# Output_des_Oszillators_Digitalisieren.net
KiCad netlist of a schematic drawn in Altium Designer
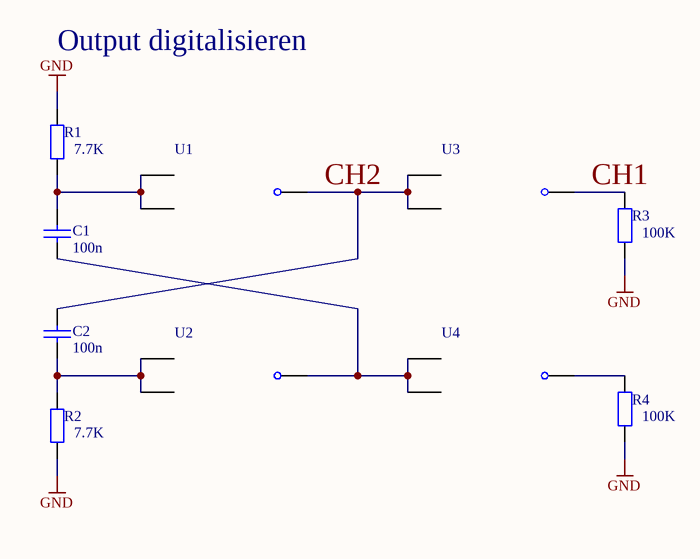
[diagram p0: Output des Oszillators Digitalisieren.SchDoc]

(export (version "E")
  (design (tool "Eeschema 10.0.6"))
  (components
    (comp (ref "C1")
      (value "100n")
      (description "Capacitor")
      (libsource (lib "Simulation Generic Components") (part "Capacitor"))
    )
    (comp (ref "C2")
      (value "100n")
      (description "Capacitor")
      (libsource (lib "Simulation Generic Components") (part "Capacitor"))
    )
    (comp (ref "R1")
      (value "7.7K")
      (footprint "AXIAL-0.4")
      (description "Resistor")
      (fields (field (name "Comment") "Res2") (field (name "PUBLISHER") "Altium Limited"))
      (libsource (lib "Miscellaneous Devices") (part "Res2"))
    )
    (comp (ref "R2")
      (value "7.7K")
      (footprint "AXIAL-0.4")
      (description "Resistor")
      (fields (field (name "Comment") "Res2") (field (name "PUBLISHER") "Altium Limited"))
      (libsource (lib "") (part "Res2_1"))
    )
    (comp (ref "R3")
      (value "100K")
      (footprint "AXIAL-0.4")
      (description "Resistor")
      (fields (field (name "Comment") "Res2") (field (name "PUBLISHER") "Altium Limited"))
      (libsource (lib "Miscellaneous Devices") (part "Res2"))
    )
    (comp (ref "R4")
      (value "100K")
      (footprint "AXIAL-0.4")
      (description "Resistor")
      (fields (field (name "Comment") "Res2") (field (name "PUBLISHER") "Altium Limited"))
      (libsource (lib "Miscellaneous Devices") (part "Res2"))
    )
    (comp (ref "U1")
      (value "Digital NAND Gate")
      (libsource (lib "Simulation Generic Components") (part "Digital NAND"))
    )
    (comp (ref "U2")
      (value "Digital NAND Gate")
      (libsource (lib "Simulation Generic Components") (part "Digital NAND"))
    )
    (comp (ref "U3")
      (value "Digital NAND Gate")
      (libsource (lib "Simulation Generic Components") (part "Digital NAND"))
    )
    (comp (ref "U4")
      (value "Digital NAND Gate")
      (libsource (lib "Simulation Generic Components") (part "Digital NAND"))
    )
  )
  (nets
    (net (code "1") (name "/CH1") (class "Default")
      (node (ref "R3") (pin "2") (pinfunction "2_2") (pintype "passive"))
      (node (ref "U3") (pin "3") (pinfunction "3_3") (pintype "passive"))
    )
    (net (code "2") (name "/CH2") (class "Default")
      (node (ref "C2") (pin "1") (pinfunction "1_1") (pintype "passive"))
      (node (ref "U1") (pin "3") (pinfunction "3_3") (pintype "passive"))
      (node (ref "U3") (pin "1") (pinfunction "1_1") (pintype "passive"))
      (node (ref "U3") (pin "2") (pinfunction "2_2") (pintype "passive"))
    )
    (net (code "3") (name "GND") (class "Default")
      (node (ref "R1") (pin "2") (pinfunction "2_2") (pintype "passive"))
      (node (ref "R2") (pin "2") (pinfunction "2_2") (pintype "passive"))
      (node (ref "R3") (pin "1") (pinfunction "1_1") (pintype "passive"))
      (node (ref "R4") (pin "1") (pinfunction "1_1") (pintype "passive"))
    )
    (net (code "4") (name "Net-(C1-Pad1)") (class "Default")
      (node (ref "C1") (pin "1") (pinfunction "1_1") (pintype "passive"))
      (node (ref "U2") (pin "3") (pinfunction "3_3") (pintype "passive"))
      (node (ref "U4") (pin "1") (pinfunction "1_1") (pintype "passive"))
      (node (ref "U4") (pin "2") (pinfunction "2_2") (pintype "passive"))
    )
    (net (code "5") (name "Net-(C1-Pad2)") (class "Default")
      (node (ref "C1") (pin "2") (pinfunction "2_2") (pintype "passive"))
      (node (ref "R1") (pin "1") (pinfunction "1_1") (pintype "passive"))
      (node (ref "U1") (pin "1") (pinfunction "1_1") (pintype "passive"))
      (node (ref "U1") (pin "2") (pinfunction "2_2") (pintype "passive"))
    )
    (net (code "6") (name "Net-(C2-Pad2)") (class "Default")
      (node (ref "C2") (pin "2") (pinfunction "2_2") (pintype "passive"))
      (node (ref "R2") (pin "1") (pinfunction "1_1") (pintype "passive"))
      (node (ref "U2") (pin "1") (pinfunction "1_1") (pintype "passive"))
      (node (ref "U2") (pin "2") (pinfunction "2_2") (pintype "passive"))
    )
    (net (code "7") (name "Net-(R4-Pad2)") (class "Default")
      (node (ref "R4") (pin "2") (pinfunction "2_2") (pintype "passive"))
      (node (ref "U4") (pin "3") (pinfunction "3_3") (pintype "passive"))
    )
  )
)
